# Sheet_Pedal.net
KiCad netlist of a schematic drawn in Altium Designer
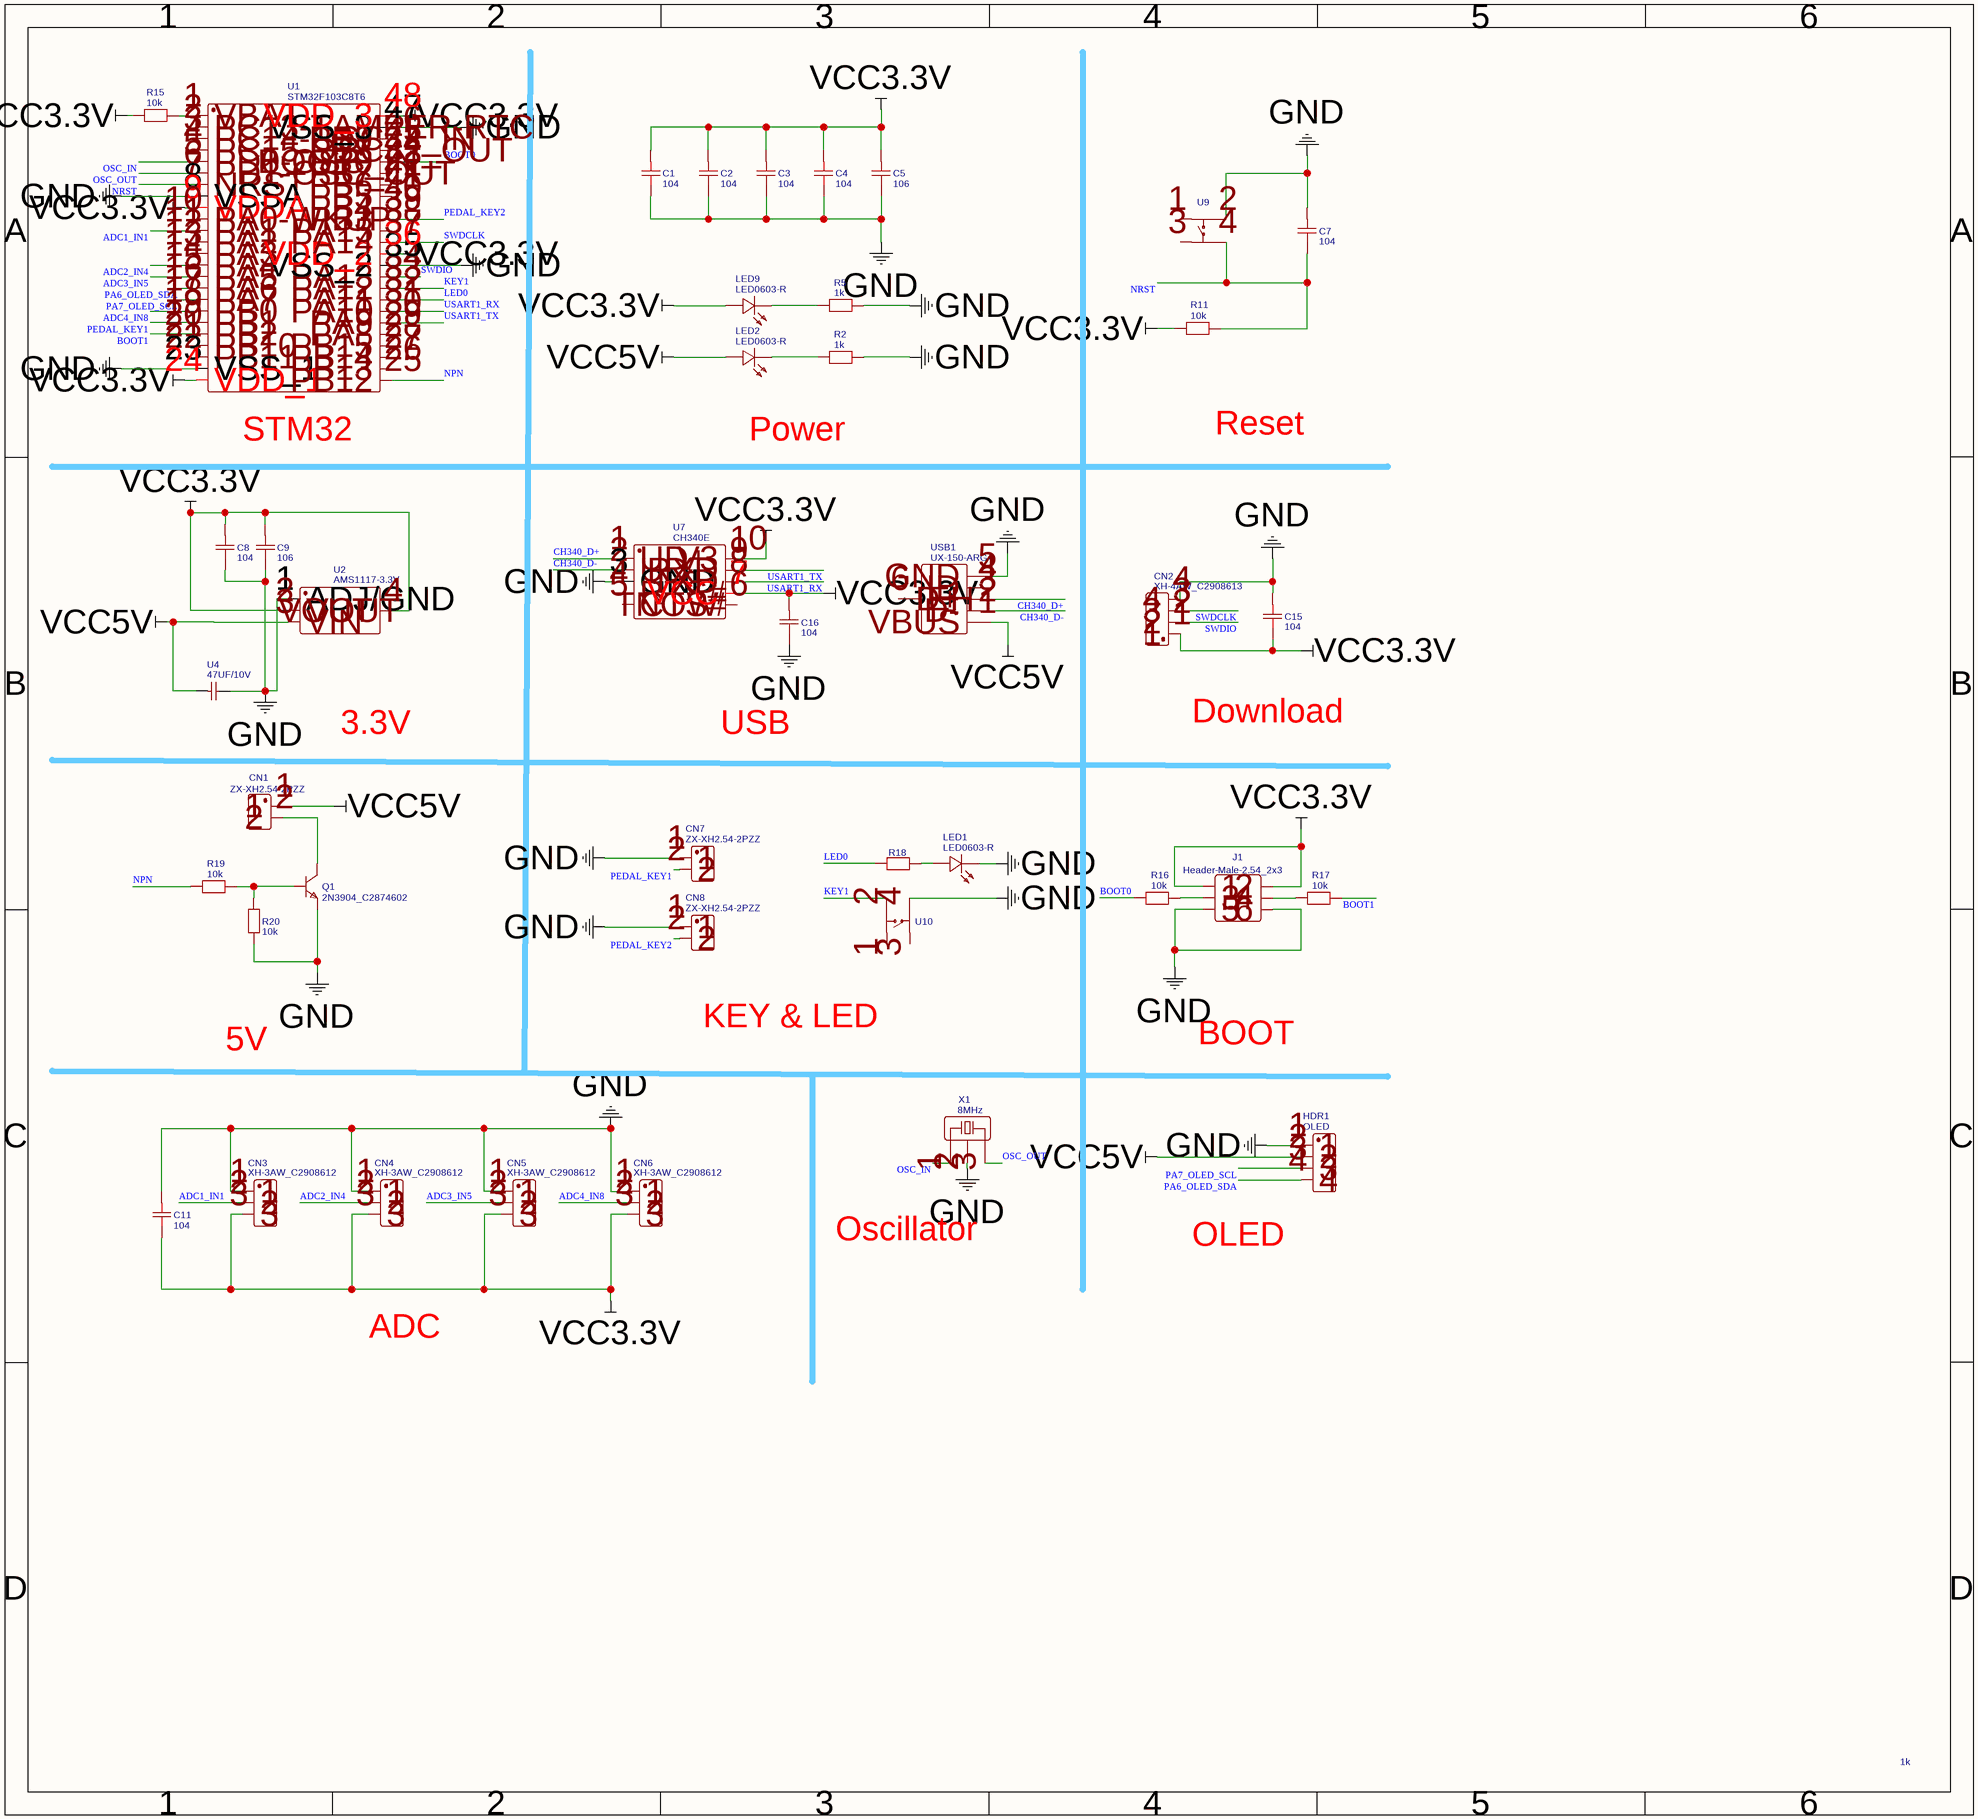
[diagram p0: Sheet_Pedal.schdoc]

(export (version "E")
  (design (tool "Eeschema 10.0.6"))
  (components
    (comp (ref "C1")
      (value "104")
      (fields (field (name "CONTRIBUTOR") "LCEDA_Lib"))
      (libsource (lib "altium-import") (part "root_1_104_"))
    )
    (comp (ref "C2")
      (value "104")
      (fields (field (name "CONTRIBUTOR") "LCEDA_Lib"))
      (libsource (lib "altium-import") (part "root_1_104_"))
    )
    (comp (ref "C3")
      (value "104")
      (fields (field (name "CONTRIBUTOR") "LCEDA_Lib"))
      (libsource (lib "altium-import") (part "root_1_104_"))
    )
    (comp (ref "C4")
      (value "104")
      (fields (field (name "CONTRIBUTOR") "LCEDA_Lib"))
      (libsource (lib "altium-import") (part "root_1_104_"))
    )
    (comp (ref "C5")
      (value "106")
      (fields (field (name "CONTRIBUTOR") "LCEDA_Lib"))
      (libsource (lib "altium-import") (part "root_1_106_"))
    )
    (comp (ref "C7")
      (value "104")
      (fields (field (name "CONTRIBUTOR") "LCEDA_Lib"))
      (libsource (lib "altium-import") (part "root_1_104_"))
    )
    (comp (ref "C8")
      (value "104")
      (fields (field (name "CONTRIBUTOR") "LCEDA_Lib"))
      (libsource (lib "altium-import") (part "root_1_104_"))
    )
    (comp (ref "C9")
      (value "106")
      (fields (field (name "CONTRIBUTOR") "LCEDA_Lib"))
      (libsource (lib "altium-import") (part "root_1_106_"))
    )
    (comp (ref "C11")
      (value "104")
      (fields (field (name "CONTRIBUTOR") "LCEDA_Lib"))
      (libsource (lib "altium-import") (part "root_1_104_"))
    )
    (comp (ref "C15")
      (value "104")
      (fields (field (name "CONTRIBUTOR") "LCEDA_Lib"))
      (libsource (lib "altium-import") (part "root_1_104_"))
    )
    (comp (ref "C16")
      (value "104")
      (fields (field (name "CONTRIBUTOR") "LCEDA_Lib"))
      (libsource (lib "altium-import") (part "root_1_104_"))
    )
    (comp (ref "CN1")
      (value "ZX-XH2.54-2PZZ")
      (fields (field (name "MANUFACTURER") "Megastar(兆星)") (field (name "CONTRIBUTOR") "lcsc"))
      (libsource (lib "altium-import") (part "root_2_ZX-XH2.54-2PZZ_"))
    )
    (comp (ref "CN2")
      (value "XH-4AW_C2908613")
      (fields
        (field (name "MANUFACTURER") "HCTL(华灿天禄)")
        (field (name "MANUFACTURER PART") "XH-4AW")
        (field (name "CONTRIBUTOR") "LCSC")
      )
      (libsource (lib "altium-import") (part "root_2_XH-4AW_C2908613_"))
    )
    (comp (ref "CN3")
      (value "XH-3AW_C2908612")
      (fields
        (field (name "MANUFACTURER") "HCTL(华灿天禄)")
        (field (name "MANUFACTURER PART") "XH-3AW")
        (field (name "CONTRIBUTOR") "LCSC")
      )
      (libsource (lib "altium-import") (part "root_0_XH-3AW_C2908612_"))
    )
    (comp (ref "CN4")
      (value "XH-3AW_C2908612")
      (fields
        (field (name "MANUFACTURER") "HCTL(华灿天禄)")
        (field (name "MANUFACTURER PART") "XH-3AW")
        (field (name "CONTRIBUTOR") "LCSC")
      )
      (libsource (lib "altium-import") (part "root_0_XH-3AW_C2908612_"))
    )
    (comp (ref "CN5")
      (value "XH-3AW_C2908612")
      (fields
        (field (name "MANUFACTURER") "HCTL(华灿天禄)")
        (field (name "MANUFACTURER PART") "XH-3AW")
        (field (name "CONTRIBUTOR") "LCSC")
      )
      (libsource (lib "altium-import") (part "root_0_XH-3AW_C2908612_"))
    )
    (comp (ref "CN6")
      (value "XH-3AW_C2908612")
      (fields
        (field (name "MANUFACTURER") "HCTL(华灿天禄)")
        (field (name "MANUFACTURER PART") "XH-3AW")
        (field (name "CONTRIBUTOR") "LCSC")
      )
      (libsource (lib "altium-import") (part "root_0_XH-3AW_C2908612_"))
    )
    (comp (ref "CN7")
      (value "ZX-XH2.54-2PZZ")
      (fields (field (name "MANUFACTURER") "Megastar(兆星)") (field (name "CONTRIBUTOR") "lcsc"))
      (libsource (lib "altium-import") (part "root_0_ZX-XH2.54-2PZZ_"))
    )
    (comp (ref "CN8")
      (value "ZX-XH2.54-2PZZ")
      (fields (field (name "MANUFACTURER") "Megastar(兆星)") (field (name "CONTRIBUTOR") "lcsc"))
      (libsource (lib "altium-import") (part "root_0_ZX-XH2.54-2PZZ_"))
    )
    (comp (ref "HDR1")
      (value "OLED")
      (fields (field (name "CONTRIBUTOR") "lcsc"))
      (libsource (lib "altium-import") (part "root_0_OLED_"))
    )
    (comp (ref "J1")
      (value "Header-Male-2.54_2x3")
      (fields (field (name "MANUFACTURER") "BOOMELE(博穆精密)") (field (name "MANUFACTURER PART") "2.54-2*3P针"))
      (libsource (lib "altium-import") (part "root_0_Header-Male-2.54_2x3_"))
    )
    (comp (ref "LED1")
      (value "LED0603-R")
      (fields (field (name "CONTRIBUTOR") "LCSC"))
      (libsource (lib "altium-import") (part "root_2_LED0603-R_"))
    )
    (comp (ref "LED2")
      (value "LED0603-R")
      (fields (field (name "CONTRIBUTOR") "LCSC"))
      (libsource (lib "altium-import") (part "root_2_LED0603-R_"))
    )
    (comp (ref "LED9")
      (value "LED0603-R")
      (fields (field (name "CONTRIBUTOR") "LCSC"))
      (libsource (lib "altium-import") (part "root_2_LED0603-R_"))
    )
    (comp (ref "Q1")
      (value "2N3904_C2874602")
      (fields
        (field (name "MANUFACTURER") "JSMSEMI(杰盛微)")
        (field (name "MANUFACTURER PART") "2N3904")
        (field (name "CONTRIBUTOR") "LCSC")
      )
      (libsource (lib "altium-import") (part "root_0_2N3904_C2874602_"))
    )
    (comp (ref "R2")
      (value "1k")
      (fields (field (name "CONTRIBUTOR") "LCEDA_Lib"))
      (libsource (lib "altium-import") (part "root_0_1k_"))
    )
    (comp (ref "R5")
      (value "1k")
      (fields (field (name "CONTRIBUTOR") "LCEDA_Lib"))
      (libsource (lib "altium-import") (part "root_0_1k_"))
    )
    (comp (ref "R11")
      (value "10k")
      (fields (field (name "CONTRIBUTOR") "LCEDA_Lib"))
      (libsource (lib "altium-import") (part "root_0_10k_"))
    )
    (comp (ref "R15")
      (value "10k")
      (fields (field (name "CONTRIBUTOR") "LCEDA_Lib"))
      (libsource (lib "altium-import") (part "root_2_10k_"))
    )
    (comp (ref "R16")
      (value "10k")
      (fields (field (name "CONTRIBUTOR") "LCEDA_Lib"))
      (libsource (lib "altium-import") (part "root_0_10k_"))
    )
    (comp (ref "R17")
      (value "10k")
      (fields (field (name "CONTRIBUTOR") "LCEDA_Lib"))
      (libsource (lib "altium-import") (part "root_0_10k_"))
    )
    (comp (ref "R18")
      (value "1k")
      (fields (field (name "CONTRIBUTOR") "LCEDA_Lib"))
      (libsource (lib "altium-import") (part "root_0_1k_"))
    )
    (comp (ref "R19")
      (value "10k")
      (fields (field (name "CONTRIBUTOR") "LCEDA_Lib"))
      (libsource (lib "altium-import") (part "root_0_10k_"))
    )
    (comp (ref "R20")
      (value "10k")
      (fields (field (name "CONTRIBUTOR") "LCEDA_Lib"))
      (libsource (lib "altium-import") (part "root_1_10k_"))
    )
    (comp (ref "U1")
      (value "STM32F103C8T6")
      (fields (field (name "MANUFACTURER") "ST(意法半导体)"))
      (libsource (lib "altium-import") (part "root_0_STM32F103C8T6_"))
    )
    (comp (ref "U2")
      (value "AMS1117-3.3V")
      (fields (field (name "MANUFACTURER") "WPMtek(维攀微)") (field (name "CONTRIBUTOR") "LCSC"))
      (libsource (lib "altium-import") (part "root_0_AMS1117-3.3V_"))
    )
    (comp (ref "U4")
      (value "47UF/10V")
      (fields (field (name "MANUFACTURER PART") "47uF/10V") (field (name "CONTRIBUTOR") "LCSC"))
      (libsource (lib "altium-import") (part "root_0_47UF/10V_"))
    )
    (comp (ref "U7")
      (value "CH340E")
      (fields (field (name "MANUFACTURER") "WCH(南京沁恒)"))
      (libsource (lib "altium-import") (part "root_0_CH340E_"))
    )
    (comp (ref "U9")
      (value "TPS645-5NC60")
      (fields (field (name "MANUFACTURER") "ROCPU Switches(台普)") (field (name "CONTRIBUTOR") "lcsc"))
      (libsource (lib "altium-import") (part "root_0_TPS645-5NC60_"))
    )
    (comp (ref "U10")
      (value "TPS645-5NC60")
      (fields (field (name "MANUFACTURER") "ROCPU Switches(台普)") (field (name "CONTRIBUTOR") "lcsc"))
      (libsource (lib "altium-import") (part "root_1_TPS645-5NC60_"))
    )
    (comp (ref "USB1")
      (value "UX-150-ARG4")
      (fields (field (name "MANUFACTURER") "XUNPU(讯普)") (field (name "CONTRIBUTOR") "LCSC"))
      (libsource (lib "altium-import") (part "root_2_UX-150-ARG4_"))
    )
    (comp (ref "X1")
      (value "8MHz")
      (fields (field (name "MANUFACTURER PART") "CSTCE8M00G52-R0") (field (name "MANUFACTURER") "muRata(村田)"))
      (libsource (lib "altium-import") (part "root_0_8MHz_"))
    )
  )
  (nets
    (net (code "1") (name "/ADC1_IN1") (class "Default")
      (node (ref "CN3") (pin "2") (pinfunction "2_2") (pintype "passive"))
      (node (ref "U1") (pin "11") (pinfunction "PA1_11") (pintype "passive"))
    )
    (net (code "2") (name "/ADC2_IN4") (class "Default")
      (node (ref "CN4") (pin "2") (pinfunction "2_2") (pintype "passive"))
      (node (ref "U1") (pin "14") (pinfunction "PA4_14") (pintype "passive"))
    )
    (net (code "3") (name "/ADC3_IN5") (class "Default")
      (node (ref "CN5") (pin "2") (pinfunction "2_2") (pintype "passive"))
      (node (ref "U1") (pin "15") (pinfunction "PA5_15") (pintype "passive"))
    )
    (net (code "4") (name "/ADC4_IN8") (class "Default")
      (node (ref "CN6") (pin "2") (pinfunction "2_2") (pintype "passive"))
      (node (ref "U1") (pin "18") (pinfunction "PB0_18") (pintype "passive"))
    )
    (net (code "5") (name "/BOOT0") (class "Default")
      (node (ref "R16") (pin "1") (pinfunction "1_1") (pintype "passive"))
      (node (ref "U1") (pin "44") (pinfunction "BOOT0_44") (pintype "passive"))
    )
    (net (code "6") (name "/BOOT1") (class "Default")
      (node (ref "R17") (pin "2") (pinfunction "2_2") (pintype "passive"))
      (node (ref "U1") (pin "20") (pinfunction "PB2_20") (pintype "passive"))
    )
    (net (code "7") (name "/CH340_D+") (class "Default")
      (node (ref "U7") (pin "1") (pinfunction "UD+_1") (pintype "passive"))
      (node (ref "USB1") (pin "3") (pinfunction "D+_3") (pintype "passive"))
    )
    (net (code "8") (name "/CH340_D-") (class "Default")
      (node (ref "U7") (pin "2") (pinfunction "UD-_2") (pintype "passive"))
      (node (ref "USB1") (pin "2") (pinfunction "D-_2") (pintype "passive"))
    )
    (net (code "9") (name "/KEY1") (class "Default")
      (node (ref "U1") (pin "33") (pinfunction "PA12_33") (pintype "passive"))
      (node (ref "U10") (pin "2") (pinfunction "2_2") (pintype "passive"))
    )
    (net (code "10") (name "/LED0") (class "Default")
      (node (ref "R18") (pin "1") (pinfunction "1_1") (pintype "passive"))
      (node (ref "U1") (pin "32") (pinfunction "PA11_32") (pintype "passive"))
    )
    (net (code "11") (name "/NPN") (class "Default")
      (node (ref "R19") (pin "1") (pinfunction "1_1") (pintype "passive"))
      (node (ref "U1") (pin "25") (pinfunction "PB12_25") (pintype "passive"))
    )
    (net (code "12") (name "/NRST") (class "Default")
      (node (ref "C7") (pin "1") (pinfunction "1_1") (pintype "passive"))
      (node (ref "R11") (pin "2") (pinfunction "2_2") (pintype "passive"))
      (node (ref "U1") (pin "7") (pinfunction "NRST_7") (pintype "passive"))
      (node (ref "U9") (pin "4") (pinfunction "4_4") (pintype "passive"))
    )
    (net (code "13") (name "/OSC_IN") (class "Default")
      (node (ref "U1") (pin "5") (pinfunction "PD0-OSC_IN_5") (pintype "passive"))
      (node (ref "X1") (pin "1") (pinfunction "1_1") (pintype "passive"))
    )
    (net (code "14") (name "/OSC_OUT") (class "Default")
      (node (ref "U1") (pin "6") (pinfunction "PD1-OSC_OUT_6") (pintype "passive"))
      (node (ref "X1") (pin "3") (pinfunction "3_3") (pintype "passive"))
    )
    (net (code "15") (name "/PA6_OLED_SDA") (class "Default")
      (node (ref "HDR1") (pin "4") (pinfunction "4_4") (pintype "passive"))
      (node (ref "U1") (pin "16") (pinfunction "PA6_16") (pintype "passive"))
    )
    (net (code "16") (name "/PA7_OLED_SCL") (class "Default")
      (node (ref "HDR1") (pin "3") (pinfunction "3_3") (pintype "passive"))
      (node (ref "U1") (pin "17") (pinfunction "PA7_17") (pintype "passive"))
    )
    (net (code "17") (name "/PEDAL_KEY1") (class "Default")
      (node (ref "CN7") (pin "2") (pinfunction "2_2") (pintype "passive"))
      (node (ref "U1") (pin "19") (pinfunction "PB1_19") (pintype "passive"))
    )
    (net (code "18") (name "/PEDAL_KEY2") (class "Default")
      (node (ref "CN8") (pin "2") (pinfunction "2_2") (pintype "passive"))
      (node (ref "U1") (pin "39") (pinfunction "PB3_39") (pintype "passive"))
    )
    (net (code "19") (name "/SWDCLK") (class "Default")
      (node (ref "CN2") (pin "3") (pinfunction "3_3") (pintype "passive"))
      (node (ref "U1") (pin "37") (pinfunction "PA14_37") (pintype "passive"))
    )
    (net (code "20") (name "/SWDIO") (class "Default")
      (node (ref "CN2") (pin "2") (pinfunction "2_2") (pintype "passive"))
      (node (ref "U1") (pin "34") (pinfunction "PA13_34") (pintype "passive"))
    )
    (net (code "21") (name "/USART1_RX") (class "Default")
      (node (ref "U1") (pin "31") (pinfunction "PA10_31") (pintype "passive"))
      (node (ref "U7") (pin "8") (pinfunction "TXD_8") (pintype "passive"))
    )
    (net (code "22") (name "/USART1_TX") (class "Default")
      (node (ref "U1") (pin "30") (pinfunction "PA9_30") (pintype "passive"))
      (node (ref "U7") (pin "9") (pinfunction "RXD_9") (pintype "passive"))
    )
    (net (code "23") (name "GND") (class "Default")
      (node (ref "C1") (pin "1") (pinfunction "1_1") (pintype "passive"))
      (node (ref "C11") (pin "2") (pinfunction "2_2") (pintype "passive"))
      (node (ref "C15") (pin "2") (pinfunction "2_2") (pintype "passive"))
      (node (ref "C16") (pin "1") (pinfunction "1_1") (pintype "passive"))
      (node (ref "C2") (pin "1") (pinfunction "1_1") (pintype "passive"))
      (node (ref "C3") (pin "1") (pinfunction "1_1") (pintype "passive"))
      (node (ref "C4") (pin "1") (pinfunction "1_1") (pintype "passive"))
      (node (ref "C5") (pin "1") (pinfunction "1_1") (pintype "passive"))
      (node (ref "C7") (pin "2") (pinfunction "2_2") (pintype "passive"))
      (node (ref "C8") (pin "1") (pinfunction "1_1") (pintype "passive"))
      (node (ref "C9") (pin "1") (pinfunction "1_1") (pintype "passive"))
      (node (ref "CN2") (pin "4") (pinfunction "4_4") (pintype "passive"))
      (node (ref "CN3") (pin "1") (pinfunction "1_1") (pintype "passive"))
      (node (ref "CN4") (pin "1") (pinfunction "1_1") (pintype "passive"))
      (node (ref "CN5") (pin "1") (pinfunction "1_1") (pintype "passive"))
      (node (ref "CN6") (pin "1") (pinfunction "1_1") (pintype "passive"))
      (node (ref "CN7") (pin "1") (pinfunction "1_1") (pintype "passive"))
      (node (ref "CN8") (pin "1") (pinfunction "1_1") (pintype "passive"))
      (node (ref "HDR1") (pin "1") (pinfunction "1_1") (pintype "passive"))
      (node (ref "J1") (pin "5") (pinfunction "5_5") (pintype "passive"))
      (node (ref "J1") (pin "6") (pinfunction "6_6") (pintype "passive"))
      (node (ref "LED1") (pin "2") (pinfunction "K_2") (pintype "passive"))
      (node (ref "Q1") (pin "1") (pinfunction "E_1") (pintype "passive"))
      (node (ref "R2") (pin "2") (pinfunction "2_2") (pintype "passive"))
      (node (ref "R20") (pin "1") (pinfunction "1_1") (pintype "passive"))
      (node (ref "R5") (pin "2") (pinfunction "2_2") (pintype "passive"))
      (node (ref "U1") (pin "23") (pinfunction "VSS_1_23") (pintype "passive"))
      (node (ref "U1") (pin "35") (pinfunction "VSS_2_35") (pintype "passive"))
      (node (ref "U1") (pin "47") (pinfunction "VSS_3_47") (pintype "passive"))
      (node (ref "U1") (pin "8") (pinfunction "VSSA_8") (pintype "passive"))
      (node (ref "U10") (pin "4") (pinfunction "4_4") (pintype "passive"))
      (node (ref "U2") (pin "1") (pinfunction "ADJ/GND_1") (pintype "passive"))
      (node (ref "U4") (pin "2") (pinfunction "2_2") (pintype "passive"))
      (node (ref "U7") (pin "3") (pinfunction "GND_3") (pintype "passive"))
      (node (ref "U9") (pin "2") (pinfunction "2_2") (pintype "passive"))
      (node (ref "USB1") (pin "5") (pinfunction "GND_5") (pintype "passive"))
      (node (ref "X1") (pin "2") (pinfunction "2_2") (pintype "passive"))
    )
    (net (code "24") (name "Net-(J1-Pad3)") (class "Default")
      (node (ref "J1") (pin "3") (pinfunction "3_3") (pintype "passive"))
      (node (ref "R16") (pin "2") (pinfunction "2_2") (pintype "passive"))
    )
    (net (code "25") (name "Net-(J1-Pad4)") (class "Default")
      (node (ref "J1") (pin "4") (pinfunction "4_4") (pintype "passive"))
      (node (ref "R17") (pin "1") (pinfunction "1_1") (pintype "passive"))
    )
    (net (code "26") (name "Net-(LED1-A)") (class "Default")
      (node (ref "LED1") (pin "1") (pinfunction "A_1") (pintype "passive"))
      (node (ref "R18") (pin "2") (pinfunction "2_2") (pintype "passive"))
    )
    (net (code "27") (name "Net-(LED2-K)") (class "Default")
      (node (ref "LED2") (pin "2") (pinfunction "K_2") (pintype "passive"))
      (node (ref "R2") (pin "1") (pinfunction "1_1") (pintype "passive"))
    )
    (net (code "28") (name "Net-(LED9-K)") (class "Default")
      (node (ref "LED9") (pin "2") (pinfunction "K_2") (pintype "passive"))
      (node (ref "R5") (pin "1") (pinfunction "1_1") (pintype "passive"))
    )
    (net (code "29") (name "Net-(Q1-B)") (class "Default")
      (node (ref "Q1") (pin "2") (pinfunction "B_2") (pintype "passive"))
      (node (ref "R19") (pin "2") (pinfunction "2_2") (pintype "passive"))
      (node (ref "R20") (pin "2") (pinfunction "2_2") (pintype "passive"))
    )
    (net (code "30") (name "Net-(Q1-C)") (class "Default")
      (node (ref "CN1") (pin "2") (pinfunction "2_2") (pintype "passive"))
      (node (ref "Q1") (pin "3") (pinfunction "C_3") (pintype "passive"))
    )
    (net (code "31") (name "Net-(U1-VBAT)") (class "Default")
      (node (ref "R15") (pin "1") (pinfunction "1_1") (pintype "passive"))
      (node (ref "U1") (pin "1") (pinfunction "VBAT_1") (pintype "passive"))
    )
    (net (code "32") (name "VCC3.3V") (class "Default")
      (node (ref "C1") (pin "2") (pinfunction "2_2") (pintype "passive"))
      (node (ref "C11") (pin "1") (pinfunction "1_1") (pintype "passive"))
      (node (ref "C15") (pin "1") (pinfunction "1_1") (pintype "passive"))
      (node (ref "C16") (pin "2") (pinfunction "2_2") (pintype "passive"))
      (node (ref "C2") (pin "2") (pinfunction "2_2") (pintype "passive"))
      (node (ref "C3") (pin "2") (pinfunction "2_2") (pintype "passive"))
      (node (ref "C4") (pin "2") (pinfunction "2_2") (pintype "passive"))
      (node (ref "C5") (pin "2") (pinfunction "2_2") (pintype "passive"))
      (node (ref "C8") (pin "2") (pinfunction "2_2") (pintype "passive"))
      (node (ref "C9") (pin "2") (pinfunction "2_2") (pintype "passive"))
      (node (ref "CN2") (pin "1") (pinfunction "1_1") (pintype "passive"))
      (node (ref "CN3") (pin "3") (pinfunction "3_3") (pintype "passive"))
      (node (ref "CN4") (pin "3") (pinfunction "3_3") (pintype "passive"))
      (node (ref "CN5") (pin "3") (pinfunction "3_3") (pintype "passive"))
      (node (ref "CN6") (pin "3") (pinfunction "3_3") (pintype "passive"))
      (node (ref "J1") (pin "1") (pinfunction "1_1") (pintype "passive"))
      (node (ref "J1") (pin "2") (pinfunction "2_2") (pintype "passive"))
      (node (ref "LED9") (pin "1") (pinfunction "A_1") (pintype "passive"))
      (node (ref "R11") (pin "1") (pinfunction "1_1") (pintype "passive"))
      (node (ref "R15") (pin "2") (pinfunction "2_2") (pintype "passive"))
      (node (ref "U1") (pin "24") (pinfunction "VDD_1_24") (pintype "passive"))
      (node (ref "U1") (pin "36") (pinfunction "VDD_2_36") (pintype "passive"))
      (node (ref "U1") (pin "48") (pinfunction "VDD_3_48") (pintype "passive"))
      (node (ref "U1") (pin "9") (pinfunction "VDDA_9") (pintype "passive"))
      (node (ref "U2") (pin "2") (pinfunction "VOUT_2") (pintype "passive"))
      (node (ref "U2") (pin "4") (pinfunction "VOUT_4") (pintype "passive"))
      (node (ref "U7") (pin "10") (pinfunction "V3_10") (pintype "passive"))
      (node (ref "U7") (pin "7") (pinfunction "VCC_7") (pintype "passive"))
    )
    (net (code "33") (name "VCC5V") (class "Default")
      (node (ref "CN1") (pin "1") (pinfunction "1_1") (pintype "passive"))
      (node (ref "HDR1") (pin "2") (pinfunction "2_2") (pintype "passive"))
      (node (ref "LED2") (pin "1") (pinfunction "A_1") (pintype "passive"))
      (node (ref "U2") (pin "3") (pinfunction "VIN_3") (pintype "passive"))
      (node (ref "U4") (pin "1") (pinfunction "1_1") (pintype "passive"))
      (node (ref "USB1") (pin "1") (pinfunction "VBUS_1") (pintype "passive"))
    )
    (net (code "34") (name "unconnected-(U1-PA0-WKUP-Pad10)") (class "Default")
      (node (ref "U1") (pin "10") (pinfunction "PA0-WKUP_10") (pintype "passive"))
    )
    (net (code "35") (name "unconnected-(U1-PA2-Pad12)") (class "Default")
      (node (ref "U1") (pin "12") (pinfunction "PA2_12") (pintype "passive"))
    )
    (net (code "36") (name "unconnected-(U1-PA3-Pad13)") (class "Default")
      (node (ref "U1") (pin "13") (pinfunction "PA3_13") (pintype "passive"))
    )
    (net (code "37") (name "unconnected-(U1-PA8-Pad29)") (class "Default")
      (node (ref "U1") (pin "29") (pinfunction "PA8_29") (pintype "passive"))
    )
    (net (code "38") (name "unconnected-(U1-PA15-Pad38)") (class "Default")
      (node (ref "U1") (pin "38") (pinfunction "PA15_38") (pintype "passive"))
    )
    (net (code "39") (name "unconnected-(U1-PB4-Pad40)") (class "Default")
      (node (ref "U1") (pin "40") (pinfunction "PB4_40") (pintype "passive"))
    )
    (net (code "40") (name "unconnected-(U1-PB5-Pad41)") (class "Default")
      (node (ref "U1") (pin "41") (pinfunction "PB5_41") (pintype "passive"))
    )
    (net (code "41") (name "unconnected-(U1-PB6-Pad42)") (class "Default")
      (node (ref "U1") (pin "42") (pinfunction "PB6_42") (pintype "passive"))
    )
    (net (code "42") (name "unconnected-(U1-PB7-Pad43)") (class "Default")
      (node (ref "U1") (pin "43") (pinfunction "PB7_43") (pintype "passive"))
    )
    (net (code "43") (name "unconnected-(U1-PB8-Pad45)") (class "Default")
      (node (ref "U1") (pin "45") (pinfunction "PB8_45") (pintype "passive"))
    )
    (net (code "44") (name "unconnected-(U1-PB9-Pad46)") (class "Default")
      (node (ref "U1") (pin "46") (pinfunction "PB9_46") (pintype "passive"))
    )
    (net (code "45") (name "unconnected-(U1-PB10-Pad21)") (class "Default")
      (node (ref "U1") (pin "21") (pinfunction "PB10_21") (pintype "passive"))
    )
    (net (code "46") (name "unconnected-(U1-PB11-Pad22)") (class "Default")
      (node (ref "U1") (pin "22") (pinfunction "PB11_22") (pintype "passive"))
    )
    (net (code "47") (name "unconnected-(U1-PB13-Pad26)") (class "Default")
      (node (ref "U1") (pin "26") (pinfunction "PB13_26") (pintype "passive"))
    )
    (net (code "48") (name "unconnected-(U1-PB14-Pad27)") (class "Default")
      (node (ref "U1") (pin "27") (pinfunction "PB14_27") (pintype "passive"))
    )
    (net (code "49") (name "unconnected-(U1-PB15-Pad28)") (class "Default")
      (node (ref "U1") (pin "28") (pinfunction "PB15_28") (pintype "passive"))
    )
    (net (code "50") (name "unconnected-(U1-PC13-TAMPER-RTC-Pad2)") (class "Default")
      (node (ref "U1") (pin "2") (pinfunction "PC13-TAMPER-RTC_2") (pintype "passive"))
    )
    (net (code "51") (name "unconnected-(U1-PC14-OSC32_IN-Pad3)") (class "Default")
      (node (ref "U1") (pin "3") (pinfunction "PC14-OSC32_IN_3") (pintype "passive"))
    )
    (net (code "52") (name "unconnected-(U1-PC15-OSC32_OUT-Pad4)") (class "Default")
      (node (ref "U1") (pin "4") (pinfunction "PC15-OSC32_OUT_4") (pintype "passive"))
    )
    (net (code "53") (name "unconnected-(U7-CTS#-Pad5)") (class "Default")
      (node (ref "U7") (pin "5") (pinfunction "CTS#_5") (pintype "passive"))
    )
    (net (code "54") (name "unconnected-(U7-RTS#-Pad4)") (class "Default")
      (node (ref "U7") (pin "4") (pinfunction "RTS#_4") (pintype "passive"))
    )
    (net (code "55") (name "unconnected-(U7-TNOW-Pad6)") (class "Default")
      (node (ref "U7") (pin "6") (pinfunction "TNOW_6") (pintype "passive"))
    )
    (net (code "56") (name "unconnected-(U9-Pad1)") (class "Default")
      (node (ref "U9") (pin "1") (pinfunction "1_1") (pintype "passive"))
    )
    (net (code "57") (name "unconnected-(U9-Pad3)") (class "Default")
      (node (ref "U9") (pin "3") (pinfunction "3_3") (pintype "passive"))
    )
    (net (code "58") (name "unconnected-(U10-Pad1)") (class "Default")
      (node (ref "U10") (pin "1") (pinfunction "1_1") (pintype "passive"))
    )
    (net (code "59") (name "unconnected-(U10-Pad3)") (class "Default")
      (node (ref "U10") (pin "3") (pinfunction "3_3") (pintype "passive"))
    )
    (net (code "60") (name "unconnected-(USB1-EH-Pad6)") (class "Default")
      (node (ref "USB1") (pin "6") (pinfunction "EH_6") (pintype "passive"))
    )
    (net (code "61") (name "unconnected-(USB1-ID-Pad4)") (class "Default")
      (node (ref "USB1") (pin "4") (pinfunction "ID_4") (pintype "passive"))
    )
  )
)
